# SkyDriver_-IMU_V2.net
KiCad netlist of a schematic drawn in Altium Designer
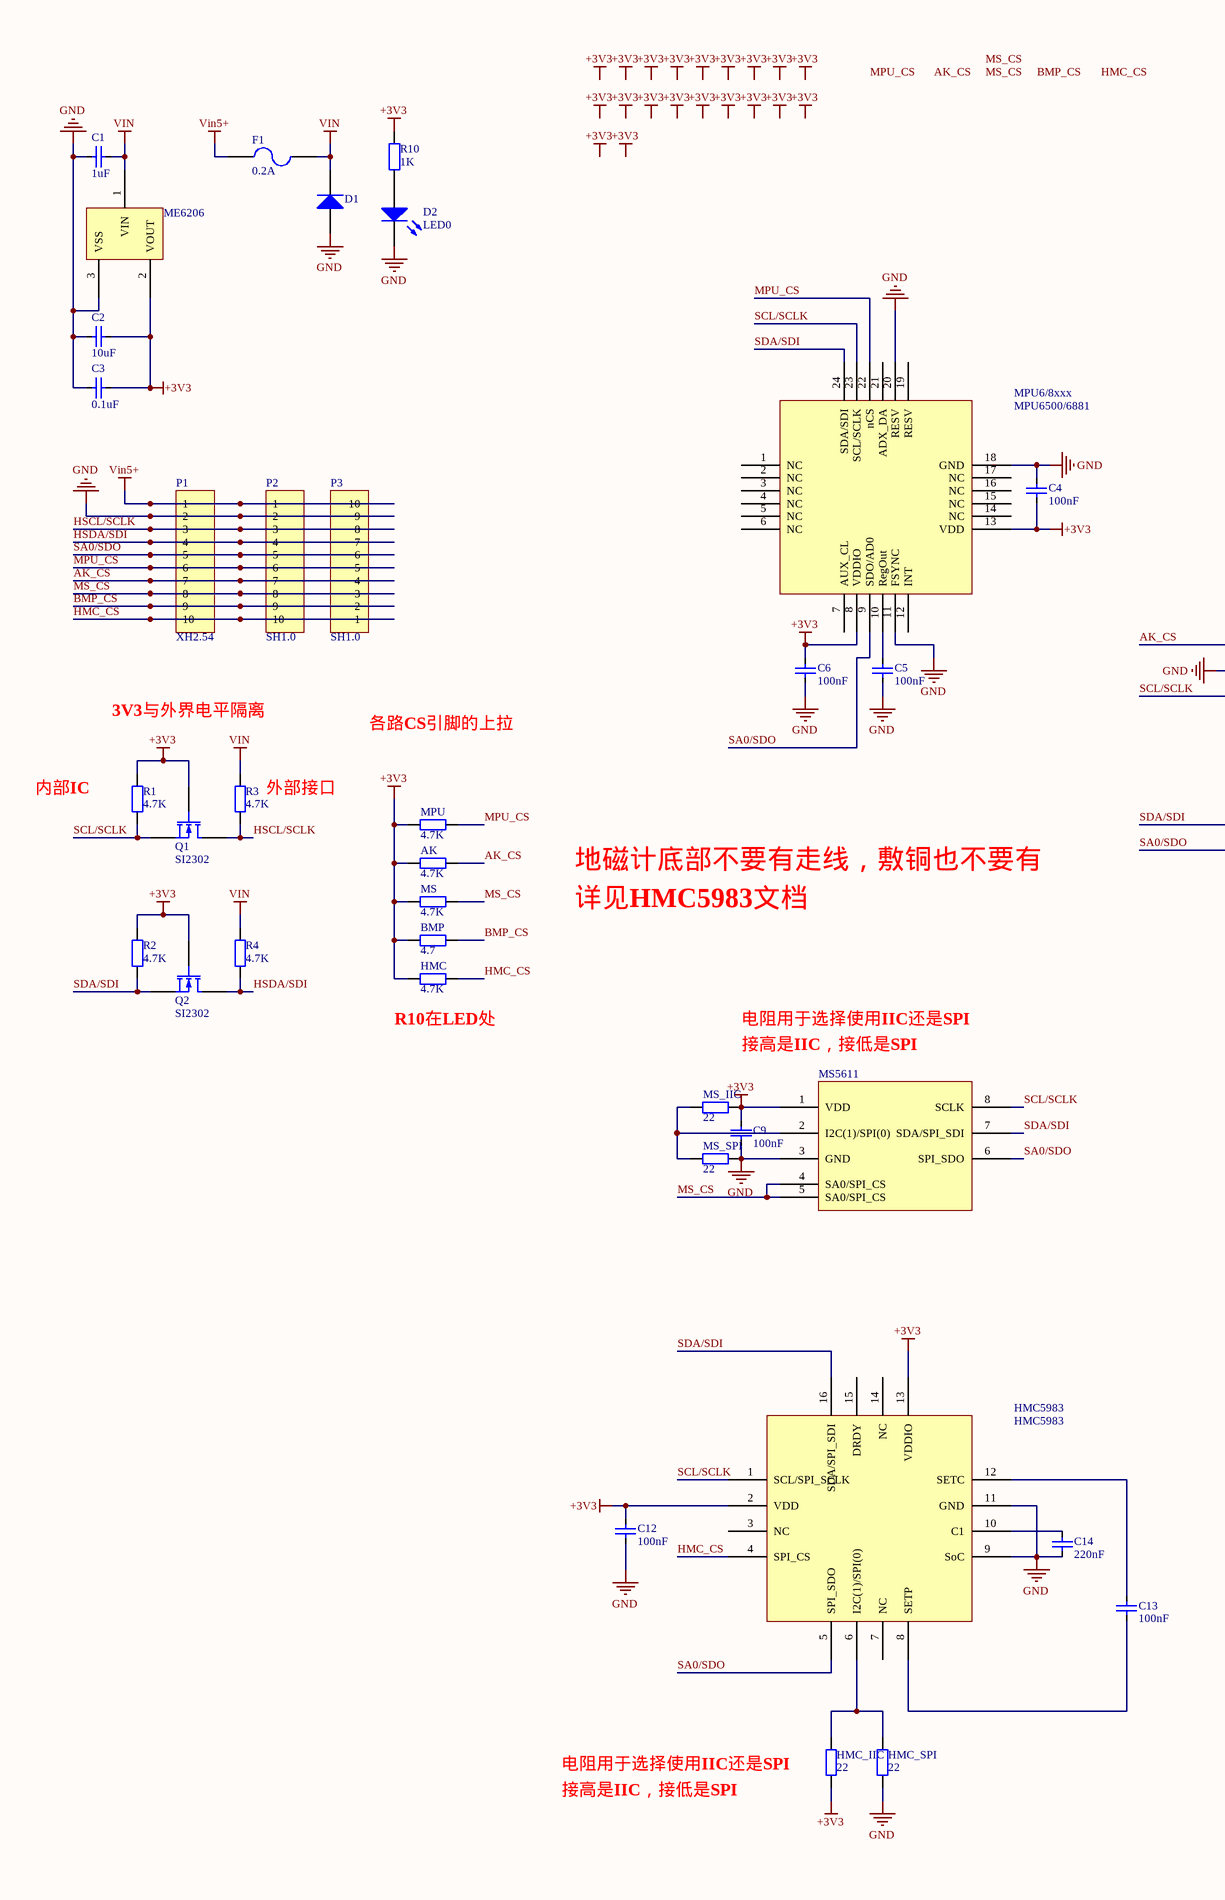
[diagram p0: SkyDriver飞行控制器-IMU板V2.SchDoc, left]
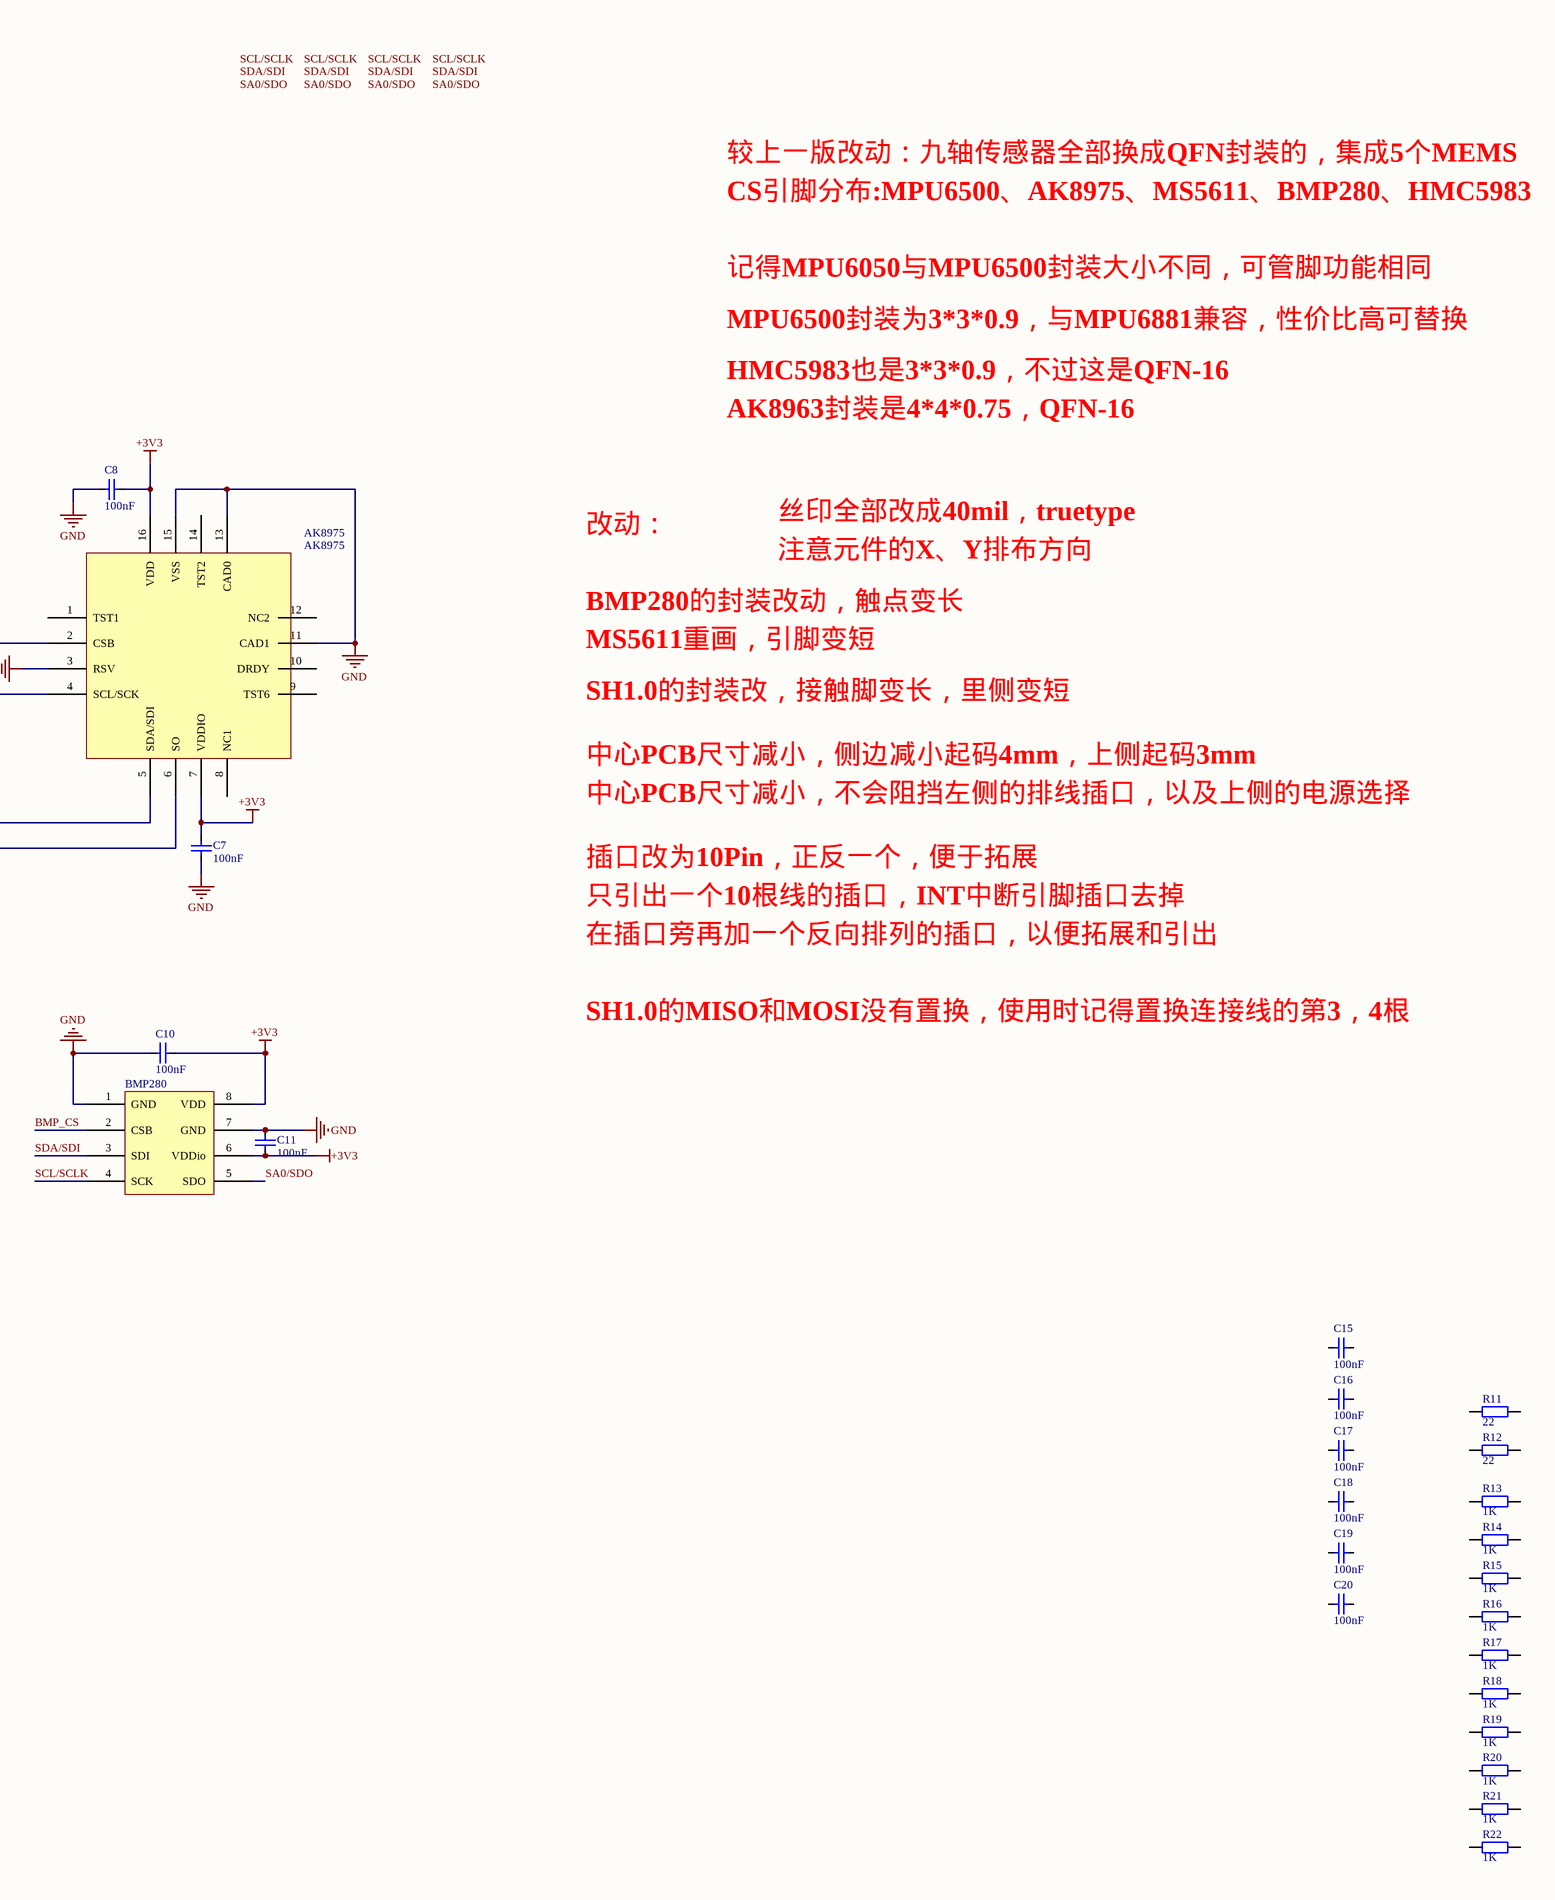
[diagram p1: SkyDriver飞行控制器-IMU板V2.SchDoc, right]

(export (version "E")
  (design (tool "Eeschema 10.0.6"))
  (components
    (comp (ref "AK")
      (value "4.7K")
      (footprint "RES_0603")
      (description "Resistor")
      (fields (field (name "Comment") "Res_0603"))
      (libsource (lib "") (part "Res_0603_3"))
    )
    (comp (ref "AK8975")
      (value "AK8975")
      (footprint "QFN16M - 4*4")
      (libsource (lib "Personal_Lib_Sch") (part "AK8975"))
    )
    (comp (ref "BMP")
      (value "4.7")
      (footprint "RES_0603")
      (description "Resistor")
      (fields (field (name "Comment") "Res_0603"))
      (libsource (lib "") (part "Res_0603_1"))
    )
    (comp (ref "BMP280")
      (value "BMP280")
      (footprint "LGA8 - BMP280")
      (libsource (lib "Personal_Lib_Sch") (part "BMP280"))
    )
    (comp (ref "C1")
      (value "1uF")
      (footprint "CAP_0603")
      (description "Capacitor")
      (fields (field (name "Comment") "Cap_0603"))
      (libsource (lib "Free Documents") (part "Cap_0603"))
    )
    (comp (ref "C2")
      (value "10uF")
      (footprint "CAP_0603")
      (description "Capacitor")
      (fields (field (name "Comment") "Cap_0603"))
      (libsource (lib "Free Documents") (part "Cap_0603"))
    )
    (comp (ref "C3")
      (value "0.1uF")
      (footprint "CAP_0603")
      (description "Capacitor")
      (fields (field (name "Comment") "Cap_0603"))
      (libsource (lib "Free Documents") (part "Cap_0603"))
    )
    (comp (ref "C4")
      (value "100nF")
      (footprint "CAP_0603")
      (description "Capacitor")
      (fields (field (name "Comment") "Cap_0603"))
      (libsource (lib "Free Documents") (part "Cap_0603"))
    )
    (comp (ref "C5")
      (value "100nF")
      (footprint "CAP_0603")
      (description "Capacitor")
      (fields (field (name "Comment") "Cap_0603"))
      (libsource (lib "Free Documents") (part "Cap_0603"))
    )
    (comp (ref "C6")
      (value "100nF")
      (footprint "CAP_0603")
      (description "Capacitor")
      (fields (field (name "Comment") "Cap_0603"))
      (libsource (lib "Free Documents") (part "Cap_0603"))
    )
    (comp (ref "C7")
      (value "100nF")
      (footprint "CAP_0603")
      (description "Capacitor")
      (fields (field (name "Comment") "Cap_0603"))
      (libsource (lib "Free Documents") (part "Cap_0603"))
    )
    (comp (ref "C8")
      (value "100nF")
      (footprint "CAP_0603")
      (description "Capacitor")
      (fields (field (name "Comment") "Cap_0603"))
      (libsource (lib "Free Documents") (part "Cap_0603"))
    )
    (comp (ref "C9")
      (value "100nF")
      (footprint "CAP_0603")
      (description "Capacitor")
      (fields (field (name "Comment") "Cap_0603"))
      (libsource (lib "Free Documents") (part "Cap_0603"))
    )
    (comp (ref "C10")
      (value "100nF")
      (footprint "CAP_0603")
      (description "Capacitor")
      (fields (field (name "Comment") "Cap_0603"))
      (libsource (lib "Free Documents") (part "Cap_0603"))
    )
    (comp (ref "C11")
      (value "100nF")
      (footprint "CAP_0603")
      (description "Capacitor")
      (fields (field (name "Comment") "Cap_0603"))
      (libsource (lib "Free Documents") (part "Cap_0603"))
    )
    (comp (ref "C12")
      (value "100nF")
      (footprint "CAP_0603")
      (description "Capacitor")
      (fields (field (name "Comment") "Cap_0603"))
      (libsource (lib "Free Documents") (part "Cap_0603"))
    )
    (comp (ref "C13")
      (value "100nF")
      (footprint "CAP_0603")
      (description "Capacitor")
      (fields (field (name "Comment") "Cap_0603"))
      (libsource (lib "Free Documents") (part "Cap_0603"))
    )
    (comp (ref "C14")
      (value "220nF")
      (footprint "CAP_0603")
      (description "Capacitor")
      (fields (field (name "Comment") "Cap_0603"))
      (libsource (lib "Free Documents") (part "Cap_0603"))
    )
    (comp (ref "C15")
      (value "100nF")
      (footprint "CAP_0603")
      (description "Capacitor")
      (fields (field (name "Comment") "Cap_0603"))
      (libsource (lib "Free Documents") (part "Cap_0603"))
    )
    (comp (ref "C16")
      (value "100nF")
      (footprint "CAP_0603")
      (description "Capacitor")
      (fields (field (name "Comment") "Cap_0603"))
      (libsource (lib "Free Documents") (part "Cap_0603"))
    )
    (comp (ref "C17")
      (value "100nF")
      (footprint "CAP_0603")
      (description "Capacitor")
      (fields (field (name "Comment") "Cap_0603"))
      (libsource (lib "Free Documents") (part "Cap_0603"))
    )
    (comp (ref "C18")
      (value "100nF")
      (footprint "CAP_0603")
      (description "Capacitor")
      (fields (field (name "Comment") "Cap_0603"))
      (libsource (lib "Free Documents") (part "Cap_0603"))
    )
    (comp (ref "C19")
      (value "100nF")
      (footprint "CAP_0603")
      (description "Capacitor")
      (fields (field (name "Comment") "Cap_0603"))
      (libsource (lib "Free Documents") (part "Cap_0603"))
    )
    (comp (ref "C20")
      (value "100nF")
      (footprint "CAP_0603")
      (description "Capacitor")
      (fields (field (name "Comment") "Cap_0603"))
      (libsource (lib "Free Documents") (part "Cap_0603"))
    )
    (comp (ref "D1")
      (value "SS14")
      (footprint "SOD323")
      (description "1 Amp General Purpose Rectifier")
      (fields (field (name "PUBLISHER") "Altium Limited"))
      (libsource (lib "Miscellaneous Devices") (part "Diode 1N4007"))
    )
    (comp (ref "D2")
      (value "LED0")
      (footprint "LED_0805")
      (description "Typical INFRARED GaAs LED")
      (fields (field (name "PUBLISHER") "Altium Limited"))
      (libsource (lib "STM32四轴") (part "LED0"))
    )
    (comp (ref "F1")
      (value "0.2A")
      (footprint "0805s")
      (description "保险丝")
      (fields (field (name "Comment") "Fuse") (field (name "PUBLISHER") "Altium Limited"))
      (libsource (lib "fszhang") (part "Fuse 2"))
    )
    (comp (ref "HMC")
      (value "4.7K")
      (footprint "RES_0603")
      (description "Resistor")
      (fields (field (name "Comment") "Res_0603"))
      (libsource (lib "") (part "Res_0603_3"))
    )
    (comp (ref "HMC5983")
      (value "HMC5983")
      (footprint "QFN16M - 3*3")
      (libsource (lib "Personal_Lib_Sch") (part "HMC5983"))
    )
    (comp (ref "HMC_IIC")
      (value "22")
      (footprint "RES_0603")
      (description "Resistor")
      (fields (field (name "Comment") "Res_0603"))
      (libsource (lib "") (part "Res_0603_2"))
    )
    (comp (ref "HMC_SPI")
      (value "22")
      (footprint "RES_0603")
      (description "Resistor")
      (fields (field (name "Comment") "Res_0603"))
      (libsource (lib "") (part "Res_0603_2"))
    )
    (comp (ref "ME6206")
      (value "ME6206")
      (footprint "sot23_M")
      (libsource (lib "Personal_Lib_Sch") (part "ME6206"))
    )
    (comp (ref "MPU")
      (value "4.7K")
      (footprint "RES_0603")
      (description "Resistor")
      (fields (field (name "Comment") "Res_0603"))
      (libsource (lib "") (part "Res_0603_3"))
    )
    (comp (ref "MPU6/8xxx")
      (value "MPU6500/6881")
      (footprint "QFN24M - 3*3")
      (libsource (lib "Personal_Lib_Sch") (part "MPU6500/6881"))
    )
    (comp (ref "MS")
      (value "4.7K")
      (footprint "RES_0603")
      (description "Resistor")
      (fields (field (name "Comment") "Res_0603"))
      (libsource (lib "") (part "Res_0603_3"))
    )
    (comp (ref "MS5611")
      (value "MS5611")
      (footprint "QFN8 - MS5611")
      (libsource (lib "Personal_Lib_Sch") (part "MS5611"))
    )
    (comp (ref "MS_IIC")
      (value "22")
      (footprint "RES_0603")
      (description "Resistor")
      (fields (field (name "Comment") "Res_0603"))
      (libsource (lib "") (part "Res_0603_1"))
    )
    (comp (ref "MS_SPI")
      (value "22")
      (footprint "RES_0603")
      (description "Resistor")
      (fields (field (name "Comment") "Res_0603"))
      (libsource (lib "") (part "Res_0603_1"))
    )
    (comp (ref "P1")
      (value "XH2.54")
      (footprint "HDR1X10")
      (description "Header, 10-Pin")
      (fields (field (name "PUBLISHER") "Altium Limited"))
      (libsource (lib "Miscellaneous Connectors") (part "Header 10"))
    )
    (comp (ref "P2")
      (value "SH1.0")
      (footprint "SH1.0_Header10")
      (description "Header, 10-Pin")
      (fields (field (name "PUBLISHER") "Altium Limited"))
      (libsource (lib "Miscellaneous Connectors") (part "Header 10"))
    )
    (comp (ref "P3")
      (value "SH1.0")
      (footprint "SH1.0_Header10")
      (description "Header, 10-Pin")
      (fields (field (name "PUBLISHER") "Altium Limited"))
      (libsource (lib "") (part "Header 10_1"))
    )
    (comp (ref "Q1")
      (value "SI2302")
      (footprint "SOT-23")
      (description "N-Channel MOSFET")
      (fields (field (name "PUBLISHER") "Altium Limited"))
      (libsource (lib "飞控工程") (part "MOSFET-N"))
    )
    (comp (ref "Q2")
      (value "SI2302")
      (footprint "SOT-23")
      (description "N-Channel MOSFET")
      (fields (field (name "PUBLISHER") "Altium Limited"))
      (libsource (lib "飞控工程") (part "MOSFET-N"))
    )
    (comp (ref "R1")
      (value "4.7K")
      (footprint "RES_0603")
      (description "Resistor")
      (fields (field (name "Comment") "Res_0603"))
      (libsource (lib "Free Documents") (part "Res_0603"))
    )
    (comp (ref "R2")
      (value "4.7K")
      (footprint "RES_0603")
      (description "Resistor")
      (fields (field (name "Comment") "Res_0603"))
      (libsource (lib "") (part "Res_0603_2"))
    )
    (comp (ref "R3")
      (value "4.7K")
      (footprint "RES_0603")
      (description "Resistor")
      (fields (field (name "Comment") "Res_0603"))
      (libsource (lib "") (part "Res_0603_2"))
    )
    (comp (ref "R4")
      (value "4.7K")
      (footprint "RES_0603")
      (description "Resistor")
      (fields (field (name "Comment") "Res_0603"))
      (libsource (lib "") (part "Res_0603_2"))
    )
    (comp (ref "R10")
      (value "1K")
      (footprint "RES_0603")
      (description "Resistor")
      (fields (field (name "Comment") "Res_0603"))
      (libsource (lib "") (part "Res_0603_2"))
    )
    (comp (ref "R11")
      (value "22")
      (footprint "RES_0603")
      (description "Resistor")
      (fields (field (name "Comment") "Res_0603"))
      (libsource (lib "") (part "Res_0603_1"))
    )
    (comp (ref "R12")
      (value "22")
      (footprint "RES_0603")
      (description "Resistor")
      (fields (field (name "Comment") "Res_0603"))
      (libsource (lib "") (part "Res_0603_1"))
    )
    (comp (ref "R13")
      (value "1K")
      (footprint "RES_0603")
      (description "Resistor")
      (fields (field (name "Comment") "Res_0603"))
      (libsource (lib "") (part "Res_0603_3"))
    )
    (comp (ref "R14")
      (value "1K")
      (footprint "RES_0603")
      (description "Resistor")
      (fields (field (name "Comment") "Res_0603"))
      (libsource (lib "") (part "Res_0603_3"))
    )
    (comp (ref "R15")
      (value "1K")
      (footprint "RES_0603")
      (description "Resistor")
      (fields (field (name "Comment") "Res_0603"))
      (libsource (lib "") (part "Res_0603_3"))
    )
    (comp (ref "R16")
      (value "1K")
      (footprint "RES_0603")
      (description "Resistor")
      (fields (field (name "Comment") "Res_0603"))
      (libsource (lib "") (part "Res_0603_3"))
    )
    (comp (ref "R17")
      (value "1K")
      (footprint "RES_0603")
      (description "Resistor")
      (fields (field (name "Comment") "Res_0603"))
      (libsource (lib "") (part "Res_0603_3"))
    )
    (comp (ref "R18")
      (value "1K")
      (footprint "RES_0603")
      (description "Resistor")
      (fields (field (name "Comment") "Res_0603"))
      (libsource (lib "") (part "Res_0603_3"))
    )
    (comp (ref "R19")
      (value "1K")
      (footprint "RES_0603")
      (description "Resistor")
      (fields (field (name "Comment") "Res_0603"))
      (libsource (lib "") (part "Res_0603_3"))
    )
    (comp (ref "R20")
      (value "1K")
      (footprint "RES_0603")
      (description "Resistor")
      (fields (field (name "Comment") "Res_0603"))
      (libsource (lib "") (part "Res_0603_3"))
    )
    (comp (ref "R21")
      (value "1K")
      (footprint "RES_0603")
      (description "Resistor")
      (fields (field (name "Comment") "Res_0603"))
      (libsource (lib "") (part "Res_0603_3"))
    )
    (comp (ref "R22")
      (value "1K")
      (footprint "RES_0603")
      (description "Resistor")
      (fields (field (name "Comment") "Res_0603"))
      (libsource (lib "") (part "Res_0603_3"))
    )
  )
  (nets
    (net (code "1") (name "+3V3") (class "Default")
      (node (ref "AK") (pin "1") (pinfunction "1_1") (pintype "passive"))
      (node (ref "AK8975") (pin "16") (pinfunction "VDD_16") (pintype "passive"))
      (node (ref "AK8975") (pin "7") (pinfunction "VDDIO_7") (pintype "passive"))
      (node (ref "BMP") (pin "2") (pinfunction "2_2") (pintype "passive"))
      (node (ref "BMP280") (pin "6") (pinfunction "VDDio_6") (pintype "passive"))
      (node (ref "BMP280") (pin "8") (pinfunction "VDD_8") (pintype "passive"))
      (node (ref "C10") (pin "1") (pinfunction "1_1") (pintype "passive"))
      (node (ref "C11") (pin "1") (pinfunction "1_1") (pintype "passive"))
      (node (ref "C12") (pin "2") (pinfunction "2_2") (pintype "passive"))
      (node (ref "C2") (pin "1") (pinfunction "1_1") (pintype "passive"))
      (node (ref "C3") (pin "1") (pinfunction "1_1") (pintype "passive"))
      (node (ref "C4") (pin "1") (pinfunction "1_1") (pintype "passive"))
      (node (ref "C6") (pin "2") (pinfunction "2_2") (pintype "passive"))
      (node (ref "C7") (pin "2") (pinfunction "2_2") (pintype "passive"))
      (node (ref "C8") (pin "1") (pinfunction "1_1") (pintype "passive"))
      (node (ref "C9") (pin "2") (pinfunction "2_2") (pintype "passive"))
      (node (ref "HMC") (pin "1") (pinfunction "1_1") (pintype "passive"))
      (node (ref "HMC5983") (pin "13") (pinfunction "VDDIO_13") (pintype "passive"))
      (node (ref "HMC5983") (pin "2") (pinfunction "VDD_2") (pintype "passive"))
      (node (ref "HMC_IIC") (pin "1") (pinfunction "1_1") (pintype "passive"))
      (node (ref "ME6206") (pin "2") (pinfunction "VOUT_2") (pintype "passive"))
      (node (ref "MPU") (pin "1") (pinfunction "1_1") (pintype "passive"))
      (node (ref "MPU6/8xxx") (pin "13") (pinfunction "VDD_13") (pintype "passive"))
      (node (ref "MPU6/8xxx") (pin "8") (pinfunction "VDDIO_8") (pintype "passive"))
      (node (ref "MS") (pin "1") (pinfunction "1_1") (pintype "passive"))
      (node (ref "MS5611") (pin "1") (pinfunction "VDD_1") (pintype "passive"))
      (node (ref "MS_IIC") (pin "1") (pinfunction "1_1") (pintype "passive"))
      (node (ref "Q1") (pin "2") (pinfunction "G_2") (pintype "passive"))
      (node (ref "Q2") (pin "2") (pinfunction "G_2") (pintype "passive"))
      (node (ref "R1") (pin "1") (pinfunction "1_1") (pintype "passive"))
      (node (ref "R10") (pin "2") (pinfunction "2_2") (pintype "passive"))
      (node (ref "R2") (pin "2") (pinfunction "2_2") (pintype "passive"))
    )
    (net (code "2") (name "/AK_CS") (class "Default")
      (node (ref "AK") (pin "2") (pinfunction "2_2") (pintype "passive"))
      (node (ref "AK8975") (pin "2") (pinfunction "CSB_2") (pintype "passive"))
      (node (ref "P1") (pin "7") (pinfunction "7_7") (pintype "passive"))
      (node (ref "P2") (pin "7") (pinfunction "7_7") (pintype "passive"))
      (node (ref "P3") (pin "4") (pinfunction "4_4") (pintype "passive"))
    )
    (net (code "3") (name "/BMP_CS") (class "Default")
      (node (ref "BMP") (pin "1") (pinfunction "1_1") (pintype "passive"))
      (node (ref "BMP280") (pin "2") (pinfunction "CSB_2") (pintype "passive"))
      (node (ref "P1") (pin "9") (pinfunction "9_9") (pintype "passive"))
      (node (ref "P2") (pin "9") (pinfunction "9_9") (pintype "passive"))
      (node (ref "P3") (pin "2") (pinfunction "2_2") (pintype "passive"))
    )
    (net (code "4") (name "/HMC_CS") (class "Default")
      (node (ref "HMC") (pin "2") (pinfunction "2_2") (pintype "passive"))
      (node (ref "HMC5983") (pin "4") (pinfunction "SPI_CS_4") (pintype "passive"))
      (node (ref "P1") (pin "10") (pinfunction "10_10") (pintype "passive"))
      (node (ref "P2") (pin "10") (pinfunction "10_10") (pintype "passive"))
      (node (ref "P3") (pin "1") (pinfunction "1_1") (pintype "passive"))
    )
    (net (code "5") (name "/HSCL{slash}SCLK") (class "Default")
      (node (ref "P1") (pin "3") (pinfunction "3_3") (pintype "passive"))
      (node (ref "P2") (pin "3") (pinfunction "3_3") (pintype "passive"))
      (node (ref "P3") (pin "8") (pinfunction "8_8") (pintype "passive"))
      (node (ref "Q1") (pin "1") (pinfunction "D_1") (pintype "passive"))
      (node (ref "R3") (pin "1") (pinfunction "1_1") (pintype "passive"))
    )
    (net (code "6") (name "/HSDA{slash}SDI") (class "Default")
      (node (ref "P1") (pin "4") (pinfunction "4_4") (pintype "passive"))
      (node (ref "P2") (pin "4") (pinfunction "4_4") (pintype "passive"))
      (node (ref "P3") (pin "7") (pinfunction "7_7") (pintype "passive"))
      (node (ref "Q2") (pin "1") (pinfunction "D_1") (pintype "passive"))
      (node (ref "R4") (pin "1") (pinfunction "1_1") (pintype "passive"))
    )
    (net (code "7") (name "/MPU_CS") (class "Default")
      (node (ref "MPU") (pin "2") (pinfunction "2_2") (pintype "passive"))
      (node (ref "MPU6/8xxx") (pin "22") (pinfunction "nCS_22") (pintype "passive"))
      (node (ref "P1") (pin "6") (pinfunction "6_6") (pintype "passive"))
      (node (ref "P2") (pin "6") (pinfunction "6_6") (pintype "passive"))
      (node (ref "P3") (pin "5") (pinfunction "5_5") (pintype "passive"))
    )
    (net (code "8") (name "/MS_CS") (class "Default")
      (node (ref "MS") (pin "2") (pinfunction "2_2") (pintype "passive"))
      (node (ref "MS5611") (pin "4") (pinfunction "SA0/SPI_CS_4") (pintype "passive"))
      (node (ref "MS5611") (pin "5") (pinfunction "SA0/SPI_CS_5") (pintype "passive"))
      (node (ref "P1") (pin "8") (pinfunction "8_8") (pintype "passive"))
      (node (ref "P2") (pin "8") (pinfunction "8_8") (pintype "passive"))
      (node (ref "P3") (pin "3") (pinfunction "3_3") (pintype "passive"))
    )
    (net (code "9") (name "/SA0{slash}SDO") (class "Default")
      (node (ref "AK8975") (pin "6") (pinfunction "SO_6") (pintype "passive"))
      (node (ref "BMP280") (pin "5") (pinfunction "SDO_5") (pintype "passive"))
      (node (ref "HMC5983") (pin "5") (pinfunction "SPI_SDO_5") (pintype "passive"))
      (node (ref "MPU6/8xxx") (pin "9") (pinfunction "SDO/AD0_9") (pintype "passive"))
      (node (ref "MS5611") (pin "6") (pinfunction "SPI_SDO_6") (pintype "passive"))
      (node (ref "P1") (pin "5") (pinfunction "5_5") (pintype "passive"))
      (node (ref "P2") (pin "5") (pinfunction "5_5") (pintype "passive"))
      (node (ref "P3") (pin "6") (pinfunction "6_6") (pintype "passive"))
    )
    (net (code "10") (name "/SCL{slash}SCLK") (class "Default")
      (node (ref "AK8975") (pin "4") (pinfunction "SCL/SCK_4") (pintype "passive"))
      (node (ref "BMP280") (pin "4") (pinfunction "SCK_4") (pintype "passive"))
      (node (ref "HMC5983") (pin "1") (pinfunction "SCL/SPI_SCLK_1") (pintype "passive"))
      (node (ref "MPU6/8xxx") (pin "23") (pinfunction "SCL/SCLK_23") (pintype "passive"))
      (node (ref "MS5611") (pin "8") (pinfunction "SCLK_8") (pintype "passive"))
      (node (ref "Q1") (pin "3") (pinfunction "S_3") (pintype "passive"))
      (node (ref "R1") (pin "2") (pinfunction "2_2") (pintype "passive"))
    )
    (net (code "11") (name "/SDA{slash}SDI") (class "Default")
      (node (ref "AK8975") (pin "5") (pinfunction "SDA/SDI_5") (pintype "passive"))
      (node (ref "BMP280") (pin "3") (pinfunction "SDI_3") (pintype "passive"))
      (node (ref "HMC5983") (pin "16") (pinfunction "SDA/SPI_SDI_16") (pintype "passive"))
      (node (ref "MPU6/8xxx") (pin "24") (pinfunction "SDA/SDI_24") (pintype "passive"))
      (node (ref "MS5611") (pin "7") (pinfunction "SDA/SPI_SDI_7") (pintype "passive"))
      (node (ref "Q2") (pin "3") (pinfunction "S_3") (pintype "passive"))
      (node (ref "R2") (pin "1") (pinfunction "1_1") (pintype "passive"))
    )
    (net (code "12") (name "GND") (class "Default")
      (node (ref "AK8975") (pin "11") (pinfunction "CAD1_11") (pintype "passive"))
      (node (ref "AK8975") (pin "13") (pinfunction "CAD0_13") (pintype "passive"))
      (node (ref "AK8975") (pin "15") (pinfunction "VSS_15") (pintype "passive"))
      (node (ref "AK8975") (pin "3") (pinfunction "RSV_3") (pintype "passive"))
      (node (ref "BMP280") (pin "1") (pinfunction "GND_1") (pintype "passive"))
      (node (ref "BMP280") (pin "7") (pinfunction "GND_7") (pintype "passive"))
      (node (ref "C1") (pin "2") (pinfunction "2_2") (pintype "passive"))
      (node (ref "C10") (pin "2") (pinfunction "2_2") (pintype "passive"))
      (node (ref "C11") (pin "2") (pinfunction "2_2") (pintype "passive"))
      (node (ref "C12") (pin "1") (pinfunction "1_1") (pintype "passive"))
      (node (ref "C14") (pin "1") (pinfunction "1_1") (pintype "passive"))
      (node (ref "C2") (pin "2") (pinfunction "2_2") (pintype "passive"))
      (node (ref "C3") (pin "2") (pinfunction "2_2") (pintype "passive"))
      (node (ref "C4") (pin "2") (pinfunction "2_2") (pintype "passive"))
      (node (ref "C5") (pin "1") (pinfunction "1_1") (pintype "passive"))
      (node (ref "C6") (pin "1") (pinfunction "1_1") (pintype "passive"))
      (node (ref "C7") (pin "1") (pinfunction "1_1") (pintype "passive"))
      (node (ref "C8") (pin "2") (pinfunction "2_2") (pintype "passive"))
      (node (ref "C9") (pin "1") (pinfunction "1_1") (pintype "passive"))
      (node (ref "D1") (pin "1") (pinfunction "A_1") (pintype "passive"))
      (node (ref "D2") (pin "2") (pinfunction "K_2") (pintype "passive"))
      (node (ref "HMC5983") (pin "11") (pinfunction "GND_11") (pintype "passive"))
      (node (ref "HMC5983") (pin "9") (pinfunction "SoC_9") (pintype "passive"))
      (node (ref "HMC_SPI") (pin "1") (pinfunction "1_1") (pintype "passive"))
      (node (ref "ME6206") (pin "3") (pinfunction "VSS_3") (pintype "passive"))
      (node (ref "MPU6/8xxx") (pin "11") (pinfunction "FSYNC_11") (pintype "passive"))
      (node (ref "MPU6/8xxx") (pin "18") (pinfunction "GND_18") (pintype "passive"))
      (node (ref "MPU6/8xxx") (pin "20") (pinfunction "RESV_20") (pintype "passive"))
      (node (ref "MS5611") (pin "3") (pinfunction "GND_3") (pintype "passive"))
      (node (ref "MS_SPI") (pin "1") (pinfunction "1_1") (pintype "passive"))
      (node (ref "P1") (pin "2") (pinfunction "2_2") (pintype "passive"))
      (node (ref "P2") (pin "2") (pinfunction "2_2") (pintype "passive"))
      (node (ref "P3") (pin "9") (pinfunction "9_9") (pintype "passive"))
    )
    (net (code "13") (name "Net-(D2-A)") (class "Default")
      (node (ref "D2") (pin "1") (pinfunction "A_1") (pintype "passive"))
      (node (ref "R10") (pin "1") (pinfunction "1_1") (pintype "passive"))
    )
    (net (code "14") (name "Net-(HMC5983-C1)") (class "Default")
      (node (ref "C14") (pin "2") (pinfunction "2_2") (pintype "passive"))
      (node (ref "HMC5983") (pin "10") (pinfunction "C1_10") (pintype "passive"))
    )
    (net (code "15") (name "Net-(HMC5983-I2C(1){slash}SPI(0))") (class "Default")
      (node (ref "HMC5983") (pin "6") (pinfunction "I2C(1)/SPI(0)_6") (pintype "passive"))
      (node (ref "HMC_IIC") (pin "2") (pinfunction "2_2") (pintype "passive"))
      (node (ref "HMC_SPI") (pin "2") (pinfunction "2_2") (pintype "passive"))
    )
    (net (code "16") (name "Net-(HMC5983-SETC)") (class "Default")
      (node (ref "C13") (pin "2") (pinfunction "2_2") (pintype "passive"))
      (node (ref "HMC5983") (pin "12") (pinfunction "SETC_12") (pintype "passive"))
    )
    (net (code "17") (name "Net-(HMC5983-SETP)") (class "Default")
      (node (ref "C13") (pin "1") (pinfunction "1_1") (pintype "passive"))
      (node (ref "HMC5983") (pin "8") (pinfunction "SETP_8") (pintype "passive"))
    )
    (net (code "18") (name "Net-(MPU6/8xxx-RegOut)") (class "Default")
      (node (ref "C5") (pin "2") (pinfunction "2_2") (pintype "passive"))
      (node (ref "MPU6/8xxx") (pin "10") (pinfunction "RegOut_10") (pintype "passive"))
    )
    (net (code "19") (name "Net-(MS5611-I2C(1){slash}SPI(0))") (class "Default")
      (node (ref "MS5611") (pin "2") (pinfunction "I2C(1)/SPI(0)_2") (pintype "passive"))
      (node (ref "MS_IIC") (pin "2") (pinfunction "2_2") (pintype "passive"))
      (node (ref "MS_SPI") (pin "2") (pinfunction "2_2") (pintype "passive"))
    )
    (net (code "20") (name "VIN") (class "Default")
      (node (ref "C1") (pin "1") (pinfunction "1_1") (pintype "passive"))
      (node (ref "D1") (pin "2") (pinfunction "K_2") (pintype "passive"))
      (node (ref "F1") (pin "2") (pinfunction "2_2") (pintype "passive"))
      (node (ref "ME6206") (pin "1") (pinfunction "VIN_1") (pintype "passive"))
      (node (ref "R3") (pin "2") (pinfunction "2_2") (pintype "passive"))
      (node (ref "R4") (pin "2") (pinfunction "2_2") (pintype "passive"))
    )
    (net (code "21") (name "Vin5+") (class "Default")
      (node (ref "F1") (pin "1") (pinfunction "1_1") (pintype "passive"))
      (node (ref "P1") (pin "1") (pinfunction "1_1") (pintype "passive"))
      (node (ref "P2") (pin "1") (pinfunction "1_1") (pintype "passive"))
      (node (ref "P3") (pin "10") (pinfunction "10_10") (pintype "passive"))
    )
    (net (code "22") (name "unconnected-(AK8975-DRDY-Pad10)") (class "Default")
      (node (ref "AK8975") (pin "10") (pinfunction "DRDY_10") (pintype "passive"))
    )
    (net (code "23") (name "unconnected-(AK8975-NC1-Pad8)") (class "Default")
      (node (ref "AK8975") (pin "8") (pinfunction "NC1_8") (pintype "passive"))
    )
    (net (code "24") (name "unconnected-(AK8975-NC2-Pad12)") (class "Default")
      (node (ref "AK8975") (pin "12") (pinfunction "NC2_12") (pintype "passive"))
    )
    (net (code "25") (name "unconnected-(AK8975-TST1-Pad1)") (class "Default")
      (node (ref "AK8975") (pin "1") (pinfunction "TST1_1") (pintype "passive"))
    )
    (net (code "26") (name "unconnected-(AK8975-TST2-Pad14)") (class "Default")
      (node (ref "AK8975") (pin "14") (pinfunction "TST2_14") (pintype "passive"))
    )
    (net (code "27") (name "unconnected-(AK8975-TST6-Pad9)") (class "Default")
      (node (ref "AK8975") (pin "9") (pinfunction "TST6_9") (pintype "passive"))
    )
    (net (code "28") (name "unconnected-(C15-Pad1)") (class "Default")
      (node (ref "C15") (pin "1") (pinfunction "1_1") (pintype "passive"))
    )
    (net (code "29") (name "unconnected-(C15-Pad2)") (class "Default")
      (node (ref "C15") (pin "2") (pinfunction "2_2") (pintype "passive"))
    )
    (net (code "30") (name "unconnected-(C16-Pad1)") (class "Default")
      (node (ref "C16") (pin "1") (pinfunction "1_1") (pintype "passive"))
    )
    (net (code "31") (name "unconnected-(C16-Pad2)") (class "Default")
      (node (ref "C16") (pin "2") (pinfunction "2_2") (pintype "passive"))
    )
    (net (code "32") (name "unconnected-(C17-Pad1)") (class "Default")
      (node (ref "C17") (pin "1") (pinfunction "1_1") (pintype "passive"))
    )
    (net (code "33") (name "unconnected-(C17-Pad2)") (class "Default")
      (node (ref "C17") (pin "2") (pinfunction "2_2") (pintype "passive"))
    )
    (net (code "34") (name "unconnected-(C18-Pad1)") (class "Default")
      (node (ref "C18") (pin "1") (pinfunction "1_1") (pintype "passive"))
    )
    (net (code "35") (name "unconnected-(C18-Pad2)") (class "Default")
      (node (ref "C18") (pin "2") (pinfunction "2_2") (pintype "passive"))
    )
    (net (code "36") (name "unconnected-(C19-Pad1)") (class "Default")
      (node (ref "C19") (pin "1") (pinfunction "1_1") (pintype "passive"))
    )
    (net (code "37") (name "unconnected-(C19-Pad2)") (class "Default")
      (node (ref "C19") (pin "2") (pinfunction "2_2") (pintype "passive"))
    )
    (net (code "38") (name "unconnected-(C20-Pad1)") (class "Default")
      (node (ref "C20") (pin "1") (pinfunction "1_1") (pintype "passive"))
    )
    (net (code "39") (name "unconnected-(C20-Pad2)") (class "Default")
      (node (ref "C20") (pin "2") (pinfunction "2_2") (pintype "passive"))
    )
    (net (code "40") (name "unconnected-(HMC5983-DRDY-Pad15)") (class "Default")
      (node (ref "HMC5983") (pin "15") (pinfunction "DRDY_15") (pintype "passive"))
    )
    (net (code "41") (name "unconnected-(HMC5983-NC-Pad3)") (class "Default")
      (node (ref "HMC5983") (pin "3") (pinfunction "NC_3") (pintype "passive"))
    )
    (net (code "42") (name "unconnected-(HMC5983-NC-Pad7)") (class "Default")
      (node (ref "HMC5983") (pin "7") (pinfunction "NC_7") (pintype "passive"))
    )
    (net (code "43") (name "unconnected-(HMC5983-NC-Pad14)") (class "Default")
      (node (ref "HMC5983") (pin "14") (pinfunction "NC_14") (pintype "passive"))
    )
    (net (code "44") (name "unconnected-(MPU6/8xxx-ADX_DA-Pad21)") (class "Default")
      (node (ref "MPU6/8xxx") (pin "21") (pinfunction "ADX_DA_21") (pintype "passive"))
    )
    (net (code "45") (name "unconnected-(MPU6/8xxx-AUX_CL-Pad7)") (class "Default")
      (node (ref "MPU6/8xxx") (pin "7") (pinfunction "AUX_CL_7") (pintype "passive"))
    )
    (net (code "46") (name "unconnected-(MPU6/8xxx-INT-Pad12)") (class "Default")
      (node (ref "MPU6/8xxx") (pin "12") (pinfunction "INT_12") (pintype "passive"))
    )
    (net (code "47") (name "unconnected-(MPU6/8xxx-NC-Pad1)") (class "Default")
      (node (ref "MPU6/8xxx") (pin "1") (pinfunction "NC_1") (pintype "passive"))
    )
    (net (code "48") (name "unconnected-(MPU6/8xxx-NC-Pad2)") (class "Default")
      (node (ref "MPU6/8xxx") (pin "2") (pinfunction "NC_2") (pintype "passive"))
    )
    (net (code "49") (name "unconnected-(MPU6/8xxx-NC-Pad3)") (class "Default")
      (node (ref "MPU6/8xxx") (pin "3") (pinfunction "NC_3") (pintype "passive"))
    )
    (net (code "50") (name "unconnected-(MPU6/8xxx-NC-Pad4)") (class "Default")
      (node (ref "MPU6/8xxx") (pin "4") (pinfunction "NC_4") (pintype "passive"))
    )
    (net (code "51") (name "unconnected-(MPU6/8xxx-NC-Pad5)") (class "Default")
      (node (ref "MPU6/8xxx") (pin "5") (pinfunction "NC_5") (pintype "passive"))
    )
    (net (code "52") (name "unconnected-(MPU6/8xxx-NC-Pad6)") (class "Default")
      (node (ref "MPU6/8xxx") (pin "6") (pinfunction "NC_6") (pintype "passive"))
    )
    (net (code "53") (name "unconnected-(MPU6/8xxx-NC-Pad14)") (class "Default")
      (node (ref "MPU6/8xxx") (pin "14") (pinfunction "NC_14") (pintype "passive"))
    )
    (net (code "54") (name "unconnected-(MPU6/8xxx-NC-Pad15)") (class "Default")
      (node (ref "MPU6/8xxx") (pin "15") (pinfunction "NC_15") (pintype "passive"))
    )
    (net (code "55") (name "unconnected-(MPU6/8xxx-NC-Pad16)") (class "Default")
      (node (ref "MPU6/8xxx") (pin "16") (pinfunction "NC_16") (pintype "passive"))
    )
    (net (code "56") (name "unconnected-(MPU6/8xxx-NC-Pad17)") (class "Default")
      (node (ref "MPU6/8xxx") (pin "17") (pinfunction "NC_17") (pintype "passive"))
    )
    (net (code "57") (name "unconnected-(MPU6/8xxx-RESV-Pad19)") (class "Default")
      (node (ref "MPU6/8xxx") (pin "19") (pinfunction "RESV_19") (pintype "passive"))
    )
    (net (code "58") (name "unconnected-(R11-Pad1)") (class "Default")
      (node (ref "R11") (pin "1") (pinfunction "1_1") (pintype "passive"))
    )
    (net (code "59") (name "unconnected-(R11-Pad2)") (class "Default")
      (node (ref "R11") (pin "2") (pinfunction "2_2") (pintype "passive"))
    )
    (net (code "60") (name "unconnected-(R12-Pad1)") (class "Default")
      (node (ref "R12") (pin "1") (pinfunction "1_1") (pintype "passive"))
    )
    (net (code "61") (name "unconnected-(R12-Pad2)") (class "Default")
      (node (ref "R12") (pin "2") (pinfunction "2_2") (pintype "passive"))
    )
    (net (code "62") (name "unconnected-(R13-Pad1)") (class "Default")
      (node (ref "R13") (pin "1") (pinfunction "1_1") (pintype "passive"))
    )
    (net (code "63") (name "unconnected-(R13-Pad2)") (class "Default")
      (node (ref "R13") (pin "2") (pinfunction "2_2") (pintype "passive"))
    )
    (net (code "64") (name "unconnected-(R14-Pad1)") (class "Default")
      (node (ref "R14") (pin "1") (pinfunction "1_1") (pintype "passive"))
    )
    (net (code "65") (name "unconnected-(R14-Pad2)") (class "Default")
      (node (ref "R14") (pin "2") (pinfunction "2_2") (pintype "passive"))
    )
    (net (code "66") (name "unconnected-(R15-Pad1)") (class "Default")
      (node (ref "R15") (pin "1") (pinfunction "1_1") (pintype "passive"))
    )
    (net (code "67") (name "unconnected-(R15-Pad2)") (class "Default")
      (node (ref "R15") (pin "2") (pinfunction "2_2") (pintype "passive"))
    )
    (net (code "68") (name "unconnected-(R16-Pad1)") (class "Default")
      (node (ref "R16") (pin "1") (pinfunction "1_1") (pintype "passive"))
    )
    (net (code "69") (name "unconnected-(R16-Pad2)") (class "Default")
      (node (ref "R16") (pin "2") (pinfunction "2_2") (pintype "passive"))
    )
    (net (code "70") (name "unconnected-(R17-Pad1)") (class "Default")
      (node (ref "R17") (pin "1") (pinfunction "1_1") (pintype "passive"))
    )
    (net (code "71") (name "unconnected-(R17-Pad2)") (class "Default")
      (node (ref "R17") (pin "2") (pinfunction "2_2") (pintype "passive"))
    )
    (net (code "72") (name "unconnected-(R18-Pad1)") (class "Default")
      (node (ref "R18") (pin "1") (pinfunction "1_1") (pintype "passive"))
    )
    (net (code "73") (name "unconnected-(R18-Pad2)") (class "Default")
      (node (ref "R18") (pin "2") (pinfunction "2_2") (pintype "passive"))
    )
    (net (code "74") (name "unconnected-(R19-Pad1)") (class "Default")
      (node (ref "R19") (pin "1") (pinfunction "1_1") (pintype "passive"))
    )
    (net (code "75") (name "unconnected-(R19-Pad2)") (class "Default")
      (node (ref "R19") (pin "2") (pinfunction "2_2") (pintype "passive"))
    )
    (net (code "76") (name "unconnected-(R20-Pad1)") (class "Default")
      (node (ref "R20") (pin "1") (pinfunction "1_1") (pintype "passive"))
    )
    (net (code "77") (name "unconnected-(R20-Pad2)") (class "Default")
      (node (ref "R20") (pin "2") (pinfunction "2_2") (pintype "passive"))
    )
    (net (code "78") (name "unconnected-(R21-Pad1)") (class "Default")
      (node (ref "R21") (pin "1") (pinfunction "1_1") (pintype "passive"))
    )
    (net (code "79") (name "unconnected-(R21-Pad2)") (class "Default")
      (node (ref "R21") (pin "2") (pinfunction "2_2") (pintype "passive"))
    )
    (net (code "80") (name "unconnected-(R22-Pad1)") (class "Default")
      (node (ref "R22") (pin "1") (pinfunction "1_1") (pintype "passive"))
    )
    (net (code "81") (name "unconnected-(R22-Pad2)") (class "Default")
      (node (ref "R22") (pin "2") (pinfunction "2_2") (pintype "passive"))
    )
  )
)
